# Slave.net
KiCad netlist of a schematic drawn in EAGLE
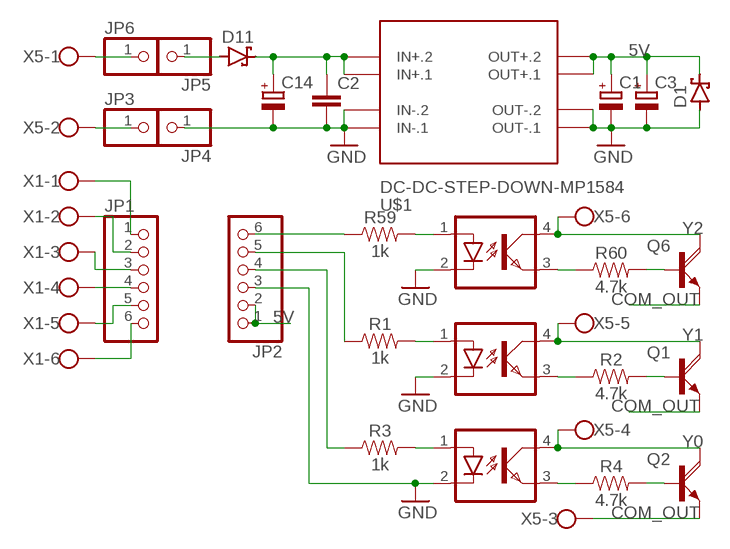
[diagram p0: schematic, sheet 1]

(export (version "E")
  (design (tool "Eeschema 10.0.6"))
  (components
    (comp (ref "C1")
      (value "CPOL-EUE2.5-7")
      (footprint "eagle-import:E2,5-7")
      (libsource (lib "eagle-import") (part "CPOL-EUE2.5-7"))
    )
    (comp (ref "C2")
      (value "C-EUC1206K")
      (footprint "eagle-import:C1206K")
      (libsource (lib "eagle-import") (part "C-EUC1206K"))
    )
    (comp (ref "C3")
      (value "CPOL-EUE2.5-7")
      (footprint "eagle-import:E2,5-7")
      (libsource (lib "eagle-import") (part "CPOL-EUE2.5-7"))
    )
    (comp (ref "C14")
      (value "CPOL-EUE2.5-7")
      (footprint "eagle-import:E2,5-7")
      (libsource (lib "eagle-import") (part "CPOL-EUE2.5-7"))
    )
    (comp (ref "D1")
      (value "SCHOTTKY-DIODESMD")
      (footprint "eagle-import:SMB")
      (libsource (lib "eagle-import") (part "SCHOTTKY-DIODESMD"))
    )
    (comp (ref "D11")
      (value "SCHOTTKY-DIODESMD")
      (footprint "eagle-import:SMB")
      (libsource (lib "eagle-import") (part "SCHOTTKY-DIODESMD"))
    )
    (comp (ref "JP1")
      (value "PINHD-1X6B")
      (footprint "eagle-import:1X06-BIG")
      (libsource (lib "eagle-import") (part "PINHD-1X6B"))
    )
    (comp (ref "JP2")
      (value "PINHD-1X6B")
      (footprint "eagle-import:1X06-BIG")
      (libsource (lib "eagle-import") (part "PINHD-1X6B"))
    )
    (comp (ref "JP3")
      (value "PINHD-1X1")
      (footprint "eagle-import:1X01")
      (libsource (lib "eagle-import") (part "PINHD-1X1"))
    )
    (comp (ref "JP4")
      (value "PINHD-1X1")
      (footprint "eagle-import:1X01")
      (libsource (lib "eagle-import") (part "PINHD-1X1"))
    )
    (comp (ref "JP5")
      (value "PINHD-1X1")
      (footprint "eagle-import:1X01")
      (libsource (lib "eagle-import") (part "PINHD-1X1"))
    )
    (comp (ref "JP6")
      (value "PINHD-1X1")
      (footprint "eagle-import:1X01")
      (libsource (lib "eagle-import") (part "PINHD-1X1"))
    )
    (comp (ref "OK1")
      (value "PC817")
      (footprint "eagle-import:DIL04")
      (fields (field (name "MPN") "PC817X4J000F"))
      (libsource (lib "eagle-import") (part "PC817"))
    )
    (comp (ref "OK2")
      (value "PC817")
      (footprint "eagle-import:DIL04")
      (fields (field (name "MPN") "PC817X4J000F"))
      (libsource (lib "eagle-import") (part "PC817"))
    )
    (comp (ref "OK14")
      (value "PC817")
      (footprint "eagle-import:DIL04")
      (fields (field (name "MPN") "PC817X4J000F"))
      (libsource (lib "eagle-import") (part "PC817"))
    )
    (comp (ref "Q1")
      (value "TIP120V")
      (footprint "eagle-import:TO220AV")
      (libsource (lib "eagle-import") (part "TIP120V"))
    )
    (comp (ref "Q2")
      (value "TIP120V")
      (footprint "eagle-import:TO220AV")
      (libsource (lib "eagle-import") (part "TIP120V"))
    )
    (comp (ref "Q6")
      (value "TIP120V")
      (footprint "eagle-import:TO220AV")
      (libsource (lib "eagle-import") (part "TIP120V"))
    )
    (comp (ref "R1")
      (value "1k")
      (footprint "eagle-import:0805")
      (libsource (lib "eagle-import") (part "0.75OHM-0805-1/4W-1%"))
    )
    (comp (ref "R2")
      (value "4.7k")
      (footprint "eagle-import:0805")
      (libsource (lib "eagle-import") (part "0.75OHM-0805-1/4W-1%"))
    )
    (comp (ref "R3")
      (value "1k")
      (footprint "eagle-import:0805")
      (libsource (lib "eagle-import") (part "0.75OHM-0805-1/4W-1%"))
    )
    (comp (ref "R4")
      (value "4.7k")
      (footprint "eagle-import:0805")
      (libsource (lib "eagle-import") (part "0.75OHM-0805-1/4W-1%"))
    )
    (comp (ref "R59")
      (value "1k")
      (footprint "eagle-import:0805")
      (libsource (lib "eagle-import") (part "0.75OHM-0805-1/4W-1%"))
    )
    (comp (ref "R60")
      (value "4.7k")
      (footprint "eagle-import:0805")
      (libsource (lib "eagle-import") (part "0.75OHM-0805-1/4W-1%"))
    )
    (comp (ref "U$1")
      (value "DC-DC-STEP-DOWN-MP1584")
      (footprint "eagle-import:DC-DC-STEP-DOWN-MP1584")
      (libsource (lib "eagle-import") (part "DC-DC-STEP-DOWN-MP1584"))
    )
    (comp (ref "X1")
      (value "W237-136")
      (footprint "eagle-import:W237-136")
      (fields (field (name "MPN") "237-136"))
      (libsource (lib "eagle-import") (part "W237-136"))
    )
    (comp (ref "X5")
      (value "W237-136")
      (footprint "eagle-import:W237-136")
      (fields (field (name "MPN") "237-136"))
      (libsource (lib "eagle-import") (part "W237-136"))
    )
  )
  (nets
    (net (code "1") (name "/5V") (class "Default")
      (node (ref "C1") (pin "+") (pinfunction "+_+") (pintype "passive"))
      (node (ref "C3") (pin "+") (pinfunction "+_+") (pintype "passive"))
      (node (ref "D1") (pin "C") (pinfunction "C_C") (pintype "passive"))
      (node (ref "JP2") (pin "1") (pinfunction "1_1") (pintype "passive"))
      (node (ref "JP2") (pin "2") (pinfunction "2_2") (pintype "passive"))
      (node (ref "U$1") (pin "OUT+.1") (pinfunction "OUT+.1_OUT+.1") (pintype "bidirectional"))
      (node (ref "U$1") (pin "OUT+.2") (pinfunction "OUT+.2_OUT+.2") (pintype "bidirectional"))
    )
    (net (code "2") (name "/COM_OUT") (class "Default")
      (node (ref "Q1") (pin "E") (pinfunction "E_E") (pintype "passive"))
      (node (ref "Q2") (pin "E") (pinfunction "E_E") (pintype "passive"))
      (node (ref "Q6") (pin "E") (pinfunction "E_E") (pintype "passive"))
      (node (ref "X5") (pin "3") (pinfunction "KL_3") (pintype "passive"))
    )
    (net (code "3") (name "/Y0") (class "Default")
      (node (ref "OK2") (pin "4") (pinfunction "COL_4") (pintype "passive"))
      (node (ref "Q2") (pin "C") (pinfunction "C_C") (pintype "passive"))
      (node (ref "X5") (pin "4") (pinfunction "KL_4") (pintype "passive"))
    )
    (net (code "4") (name "/Y1") (class "Default")
      (node (ref "OK1") (pin "4") (pinfunction "COL_4") (pintype "passive"))
      (node (ref "Q1") (pin "C") (pinfunction "C_C") (pintype "passive"))
      (node (ref "X5") (pin "5") (pinfunction "KL_5") (pintype "passive"))
    )
    (net (code "5") (name "/Y2") (class "Default")
      (node (ref "OK14") (pin "4") (pinfunction "COL_4") (pintype "passive"))
      (node (ref "Q6") (pin "C") (pinfunction "C_C") (pintype "passive"))
      (node (ref "X5") (pin "6") (pinfunction "KL_6") (pintype "passive"))
    )
    (net (code "6") (name "GND") (class "Default")
      (node (ref "C1") (pin "-") (pinfunction "-_-") (pintype "passive"))
      (node (ref "C14") (pin "-") (pinfunction "-_-") (pintype "passive"))
      (node (ref "C2") (pin "2") (pinfunction "2_2") (pintype "passive"))
      (node (ref "C3") (pin "-") (pinfunction "-_-") (pintype "passive"))
      (node (ref "D1") (pin "A") (pinfunction "A_A") (pintype "passive"))
      (node (ref "JP2") (pin "3") (pinfunction "3_3") (pintype "passive"))
      (node (ref "JP4") (pin "1") (pinfunction "1_1") (pintype "passive"))
      (node (ref "OK1") (pin "2") (pinfunction "C_2") (pintype "passive"))
      (node (ref "OK14") (pin "2") (pinfunction "C_2") (pintype "passive"))
      (node (ref "OK2") (pin "2") (pinfunction "C_2") (pintype "passive"))
      (node (ref "U$1") (pin "IN-.1") (pinfunction "IN-.1_IN-.1") (pintype "bidirectional"))
      (node (ref "U$1") (pin "IN-.2") (pinfunction "IN-.2_IN-.2") (pintype "bidirectional"))
      (node (ref "U$1") (pin "OUT-.1") (pinfunction "OUT-.1_OUT-.1") (pintype "bidirectional"))
      (node (ref "U$1") (pin "OUT-.2") (pinfunction "OUT-.2_OUT-.2") (pintype "bidirectional"))
    )
    (net (code "7") (name "Net-(C14-Pad+)") (class "Default")
      (node (ref "C14") (pin "+") (pinfunction "+_+") (pintype "passive"))
      (node (ref "C2") (pin "1") (pinfunction "1_1") (pintype "passive"))
      (node (ref "D11") (pin "C") (pinfunction "C_C") (pintype "passive"))
      (node (ref "U$1") (pin "IN+.1") (pinfunction "IN+.1_IN+.1") (pintype "bidirectional"))
      (node (ref "U$1") (pin "IN+.2") (pinfunction "IN+.2_IN+.2") (pintype "bidirectional"))
    )
    (net (code "8") (name "Net-(D11-PadA)") (class "Default")
      (node (ref "D11") (pin "A") (pinfunction "A_A") (pintype "passive"))
      (node (ref "JP5") (pin "1") (pinfunction "1_1") (pintype "passive"))
    )
    (net (code "9") (name "Net-(JP2-Pad4)") (class "Default")
      (node (ref "JP2") (pin "4") (pinfunction "4_4") (pintype "passive"))
      (node (ref "R3") (pin "1") (pinfunction "1_1") (pintype "passive"))
    )
    (net (code "10") (name "Net-(JP2-Pad5)") (class "Default")
      (node (ref "JP2") (pin "5") (pinfunction "5_5") (pintype "passive"))
      (node (ref "R1") (pin "1") (pinfunction "1_1") (pintype "passive"))
    )
    (net (code "11") (name "Net-(JP2-Pad6)") (class "Default")
      (node (ref "JP2") (pin "6") (pinfunction "6_6") (pintype "passive"))
      (node (ref "R59") (pin "1") (pinfunction "1_1") (pintype "passive"))
    )
    (net (code "12") (name "Net-(OK1-A)") (class "Default")
      (node (ref "OK1") (pin "1") (pinfunction "A_1") (pintype "passive"))
      (node (ref "R1") (pin "2") (pinfunction "2_2") (pintype "passive"))
    )
    (net (code "13") (name "Net-(OK1-EMIT)") (class "Default")
      (node (ref "OK1") (pin "3") (pinfunction "EMIT_3") (pintype "passive"))
      (node (ref "R2") (pin "1") (pinfunction "1_1") (pintype "passive"))
    )
    (net (code "14") (name "Net-(OK2-A)") (class "Default")
      (node (ref "OK2") (pin "1") (pinfunction "A_1") (pintype "passive"))
      (node (ref "R3") (pin "2") (pinfunction "2_2") (pintype "passive"))
    )
    (net (code "15") (name "Net-(OK2-EMIT)") (class "Default")
      (node (ref "OK2") (pin "3") (pinfunction "EMIT_3") (pintype "passive"))
      (node (ref "R4") (pin "1") (pinfunction "1_1") (pintype "passive"))
    )
    (net (code "16") (name "Net-(OK14-A)") (class "Default")
      (node (ref "OK14") (pin "1") (pinfunction "A_1") (pintype "passive"))
      (node (ref "R59") (pin "2") (pinfunction "2_2") (pintype "passive"))
    )
    (net (code "17") (name "Net-(OK14-EMIT)") (class "Default")
      (node (ref "OK14") (pin "3") (pinfunction "EMIT_3") (pintype "passive"))
      (node (ref "R60") (pin "1") (pinfunction "1_1") (pintype "passive"))
    )
    (net (code "18") (name "Net-(Q1-PadB)") (class "Default")
      (node (ref "Q1") (pin "B") (pinfunction "B_B") (pintype "passive"))
      (node (ref "R2") (pin "2") (pinfunction "2_2") (pintype "passive"))
    )
    (net (code "19") (name "Net-(Q2-PadB)") (class "Default")
      (node (ref "Q2") (pin "B") (pinfunction "B_B") (pintype "passive"))
      (node (ref "R4") (pin "2") (pinfunction "2_2") (pintype "passive"))
    )
    (net (code "20") (name "Net-(Q6-PadB)") (class "Default")
      (node (ref "Q6") (pin "B") (pinfunction "B_B") (pintype "passive"))
      (node (ref "R60") (pin "2") (pinfunction "2_2") (pintype "passive"))
    )
    (net (code "21") (name "Net-(X1A-KL)") (class "Default")
      (node (ref "JP1") (pin "1") (pinfunction "1_1") (pintype "passive"))
      (node (ref "X1") (pin "1") (pinfunction "KL_1") (pintype "passive"))
    )
    (net (code "22") (name "Net-(X1B-KL)") (class "Default")
      (node (ref "JP1") (pin "2") (pinfunction "2_2") (pintype "passive"))
      (node (ref "X1") (pin "2") (pinfunction "KL_2") (pintype "passive"))
    )
    (net (code "23") (name "Net-(X1C-KL)") (class "Default")
      (node (ref "JP1") (pin "3") (pinfunction "3_3") (pintype "passive"))
      (node (ref "X1") (pin "3") (pinfunction "KL_3") (pintype "passive"))
    )
    (net (code "24") (name "Net-(X1D-KL)") (class "Default")
      (node (ref "JP1") (pin "4") (pinfunction "4_4") (pintype "passive"))
      (node (ref "X1") (pin "4") (pinfunction "KL_4") (pintype "passive"))
    )
    (net (code "25") (name "Net-(X1E-KL)") (class "Default")
      (node (ref "JP1") (pin "5") (pinfunction "5_5") (pintype "passive"))
      (node (ref "X1") (pin "5") (pinfunction "KL_5") (pintype "passive"))
    )
    (net (code "26") (name "Net-(X1F-KL)") (class "Default")
      (node (ref "JP1") (pin "6") (pinfunction "6_6") (pintype "passive"))
      (node (ref "X1") (pin "6") (pinfunction "KL_6") (pintype "passive"))
    )
    (net (code "27") (name "Net-(X5A-KL)") (class "Default")
      (node (ref "JP6") (pin "1") (pinfunction "1_1") (pintype "passive"))
      (node (ref "X5") (pin "1") (pinfunction "KL_1") (pintype "passive"))
    )
    (net (code "28") (name "Net-(X5B-KL)") (class "Default")
      (node (ref "JP3") (pin "1") (pinfunction "1_1") (pintype "passive"))
      (node (ref "X5") (pin "2") (pinfunction "KL_2") (pintype "passive"))
    )
  )
)
